# MAX30208_HSP3_DEMO_B.net
KiCad netlist of a schematic drawn in EAGLE
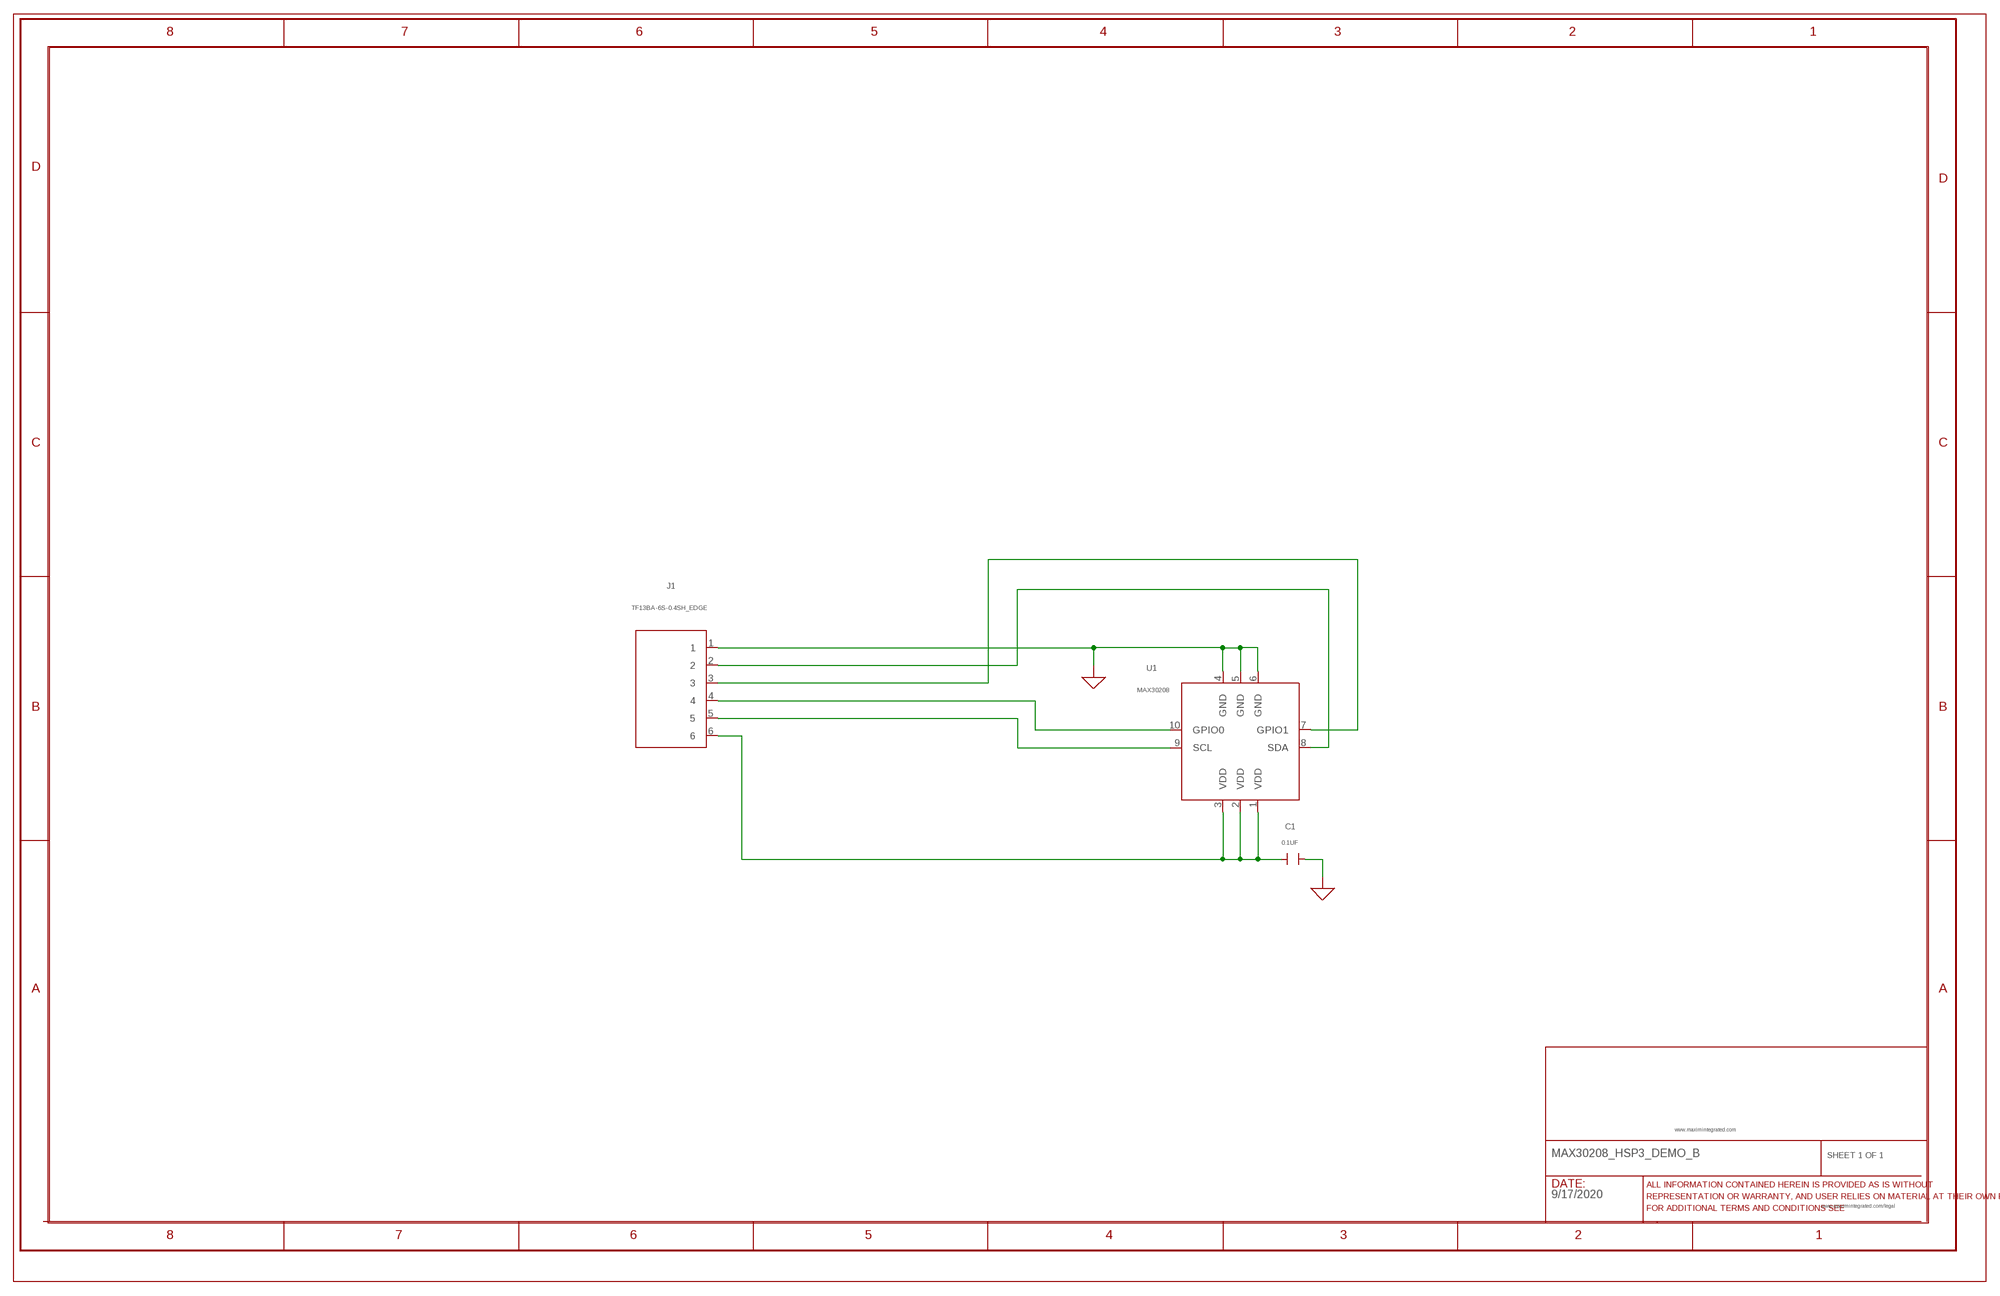
[diagram p0: schematic, sheet 1]

(export (version "E")
  (design (tool "Eeschema 10.0.6"))
  (components
    (comp (ref "C1")
      (value "0.1UF")
      (footprint "eagle-import:CAPC0603X33M")
      (description "CAP: SMT (0201): 0.1UF: 10%: 25V: X6S: CERAMIC")
      (fields
        (field (name "CAP") "1.00E-07")
        (field (name "CASE") "SMT (0201)")
        (field (name "MANUFACTURER") "MURATA")
        (field (name "MATERIAL_TYPE") "CERAMIC CHIP")
        (field (name "MAXINV") "20-000U1-DA39")
        (field (name "MFG_PART_NUMBER") "GRM033C81E104KE14")
        (field (name "OriginalSymbolOrigin") "(-50,50)")
        (field (name "PACK_TYPE") "0201CAPM")
        (field (name "PHYS_PAGE") "1")
        (field (name "REFLOW") "-")
        (field (name "TEMP_RANGE") "-55 DEGC TO +105 DEGC")
        (field (name "TOLERANCE") "10%")
        (field (name "VER") "1")
        (field (name "VLOG_PARAM01") "CAP:INTEGER")
        (field (name "VOLTAGE_RATING") "25V")
      )
      (libsource (lib "eagle-import") (part "CAP_NP"))
    )
    (comp (ref "J1")
      (value "TF13BA-6S-0.4SH_EDGE")
      (footprint "eagle-import:HRSC_TF13BA-6S-0_4SH_EDGE")
      (description "CONNECTOR: MALE: SMT: TF13BA SERIES: FPC/FFC CONNECTOR: 6PINS: NOTE: EDGE CONNECTOR TO BE USED AT THE END OF A FLEX BOARD")
      (fields
        (field (name "MANUFACTURER") "HIROSE ELECTRIC CO LTD")
        (field (name "MAXINV") "N/A")
        (field (name "MFG_PART_NUMBER") "TF13BA-6S-0.4SH_EDGE")
        (field (name "OriginalSymbolOrigin") "(-150,275)")
        (field (name "PACK_TYPE") "SMD_EDGE")
        (field (name "PHYS_PAGE") "1")
        (field (name "REFLOW") "-")
        (field (name "TEMP_RANGE") "N/A")
        (field (name "TOLERANCE") "N/A")
        (field (name "VER") "1")
        (field (name "VOLTAGE_RATING") "N/A")
      )
      (libsource (lib "eagle-import") (part "TF13BA-6S"))
    )
    (comp (ref "U1")
      (value "MAX30208")
      (footprint "eagle-import:MAX_90-100101_1-10")
      (description "EVKIT PART - IC: MAX30208: PACKAGE OUTLINE DRAWING: 21-100265: LGA10")
      (fields
        (field (name "MANUFACTURER") "MAXIM")
        (field (name "MAXINV") "N/A")
        (field (name "MFG_PART_NUMBER") "MAX30208")
        (field (name "OriginalSymbolOrigin") "(-325,300)")
        (field (name "PACK_TYPE") "LGA10")
        (field (name "PHYS_PAGE") "1")
        (field (name "REFLOW") "-")
        (field (name "SEC_TYPE") "LGA10")
        (field (name "TEMP_RANGE") "N/A")
        (field (name "TOLERANCE") "N/A")
        (field (name "VER") "1")
        (field (name "VOLTAGE_RATING") "N/A")
      )
      (libsource (lib "eagle-import") (part "EK_MAX30208"))
    )
  )
  (nets
    (net (code "1") (name "GND_SIGNAL") (class "Default")
      (node (ref "C1") (pin "2") (pinfunction "2_2") (pintype "bidirectional"))
      (node (ref "J1") (pin "1") (pinfunction "1_1") (pintype "bidirectional"))
      (node (ref "U1") (pin "4") (pinfunction "GND_4") (pintype "bidirectional"))
      (node (ref "U1") (pin "5") (pinfunction "GND_5") (pintype "bidirectional"))
      (node (ref "U1") (pin "6") (pinfunction "GND_6") (pintype "bidirectional"))
    )
    (net (code "2") (name "Net-(C1-Pad1)") (class "Default")
      (node (ref "C1") (pin "1") (pinfunction "1_1") (pintype "bidirectional"))
      (node (ref "J1") (pin "6") (pinfunction "6_6") (pintype "bidirectional"))
      (node (ref "U1") (pin "1") (pinfunction "VDD_1") (pintype "bidirectional"))
      (node (ref "U1") (pin "2") (pinfunction "VDD_2") (pintype "bidirectional"))
      (node (ref "U1") (pin "3") (pinfunction "VDD_3") (pintype "bidirectional"))
    )
    (net (code "3") (name "Net-(U1-GPIO0)") (class "Default")
      (node (ref "J1") (pin "4") (pinfunction "4_4") (pintype "bidirectional"))
      (node (ref "U1") (pin "10") (pinfunction "GPIO0_10") (pintype "bidirectional"))
    )
    (net (code "4") (name "Net-(U1-GPIO1)") (class "Default")
      (node (ref "J1") (pin "3") (pinfunction "3_3") (pintype "bidirectional"))
      (node (ref "U1") (pin "7") (pinfunction "GPIO1_7") (pintype "bidirectional"))
    )
    (net (code "5") (name "Net-(U1-SCL)") (class "Default")
      (node (ref "J1") (pin "5") (pinfunction "5_5") (pintype "bidirectional"))
      (node (ref "U1") (pin "9") (pinfunction "SCL_9") (pintype "bidirectional"))
    )
    (net (code "6") (name "Net-(U1-SDA)") (class "Default")
      (node (ref "J1") (pin "2") (pinfunction "2_2") (pintype "bidirectional"))
      (node (ref "U1") (pin "8") (pinfunction "SDA_8") (pintype "bidirectional"))
    )
  )
)
